# PM12_P1V0.net
KiCad netlist of a schematic drawn in Altium Designer
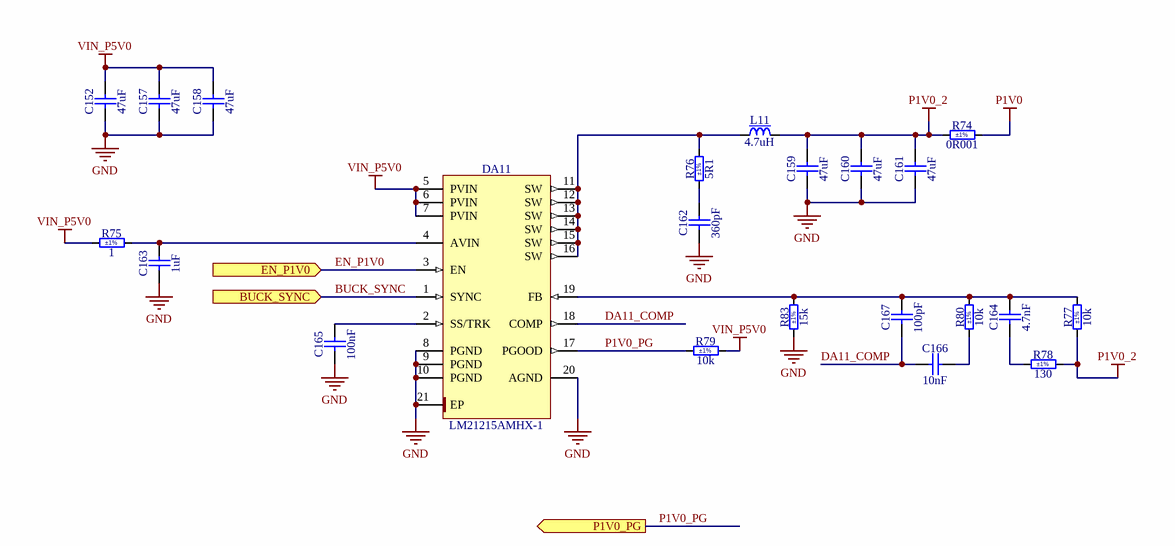
[diagram p0: PM12_P1V0.SchDoc]

(export (version "E")
  (design (tool "Eeschema 10.0.6"))
  (components
    (comp (ref "C152")
      (value "47uF")
      (footprint "CAPC3225X270N")
      (description "Non-polarised capacitor")
      (fields
        (field (name "PART NUMBER") "CC1210_47UF_16V_20%_X5R")
        (field (name "VOLTAGE") "16V")
        (field (name "AUTHOR") "CERN DEM MR")
      )
      (libsource (lib "Capacitors") (part "Capacitor - non polarized"))
    )
    (comp (ref "C157")
      (value "47uF")
      (footprint "CAPC3225X270N")
      (description "Non-polarised capacitor")
      (fields
        (field (name "PART NUMBER") "CC1210_47UF_16V_20%_X5R")
        (field (name "VOLTAGE") "16V")
        (field (name "AUTHOR") "CERN DEM MR")
      )
      (libsource (lib "Capacitors") (part "Capacitor - non polarized"))
    )
    (comp (ref "C158")
      (value "47uF")
      (footprint "CAPC3225X270N")
      (description "Non-polarised capacitor")
      (fields
        (field (name "PART NUMBER") "CC1210_47UF_16V_20%_X5R")
        (field (name "VOLTAGE") "16V")
        (field (name "AUTHOR") "CERN DEM MR")
      )
      (libsource (lib "Capacitors") (part "Capacitor - non polarized"))
    )
    (comp (ref "C159")
      (value "47uF")
      (footprint "CAPC3225X270N")
      (description "Non-polarised capacitor")
      (fields
        (field (name "PART NUMBER") "CC1210_47UF_16V_20%_X5R")
        (field (name "VOLTAGE") "16V")
        (field (name "AUTHOR") "CERN DEM MR")
      )
      (libsource (lib "Capacitors") (part "Capacitor - non polarized"))
    )
    (comp (ref "C160")
      (value "47uF")
      (footprint "CAPC3225X270N")
      (description "Non-polarised capacitor")
      (fields
        (field (name "PART NUMBER") "CC1210_47UF_16V_20%_X5R")
        (field (name "VOLTAGE") "16V")
        (field (name "AUTHOR") "CERN DEM MR")
      )
      (libsource (lib "Capacitors") (part "Capacitor - non polarized"))
    )
    (comp (ref "C161")
      (value "47uF")
      (footprint "CAPC3225X270N")
      (description "Non-polarised capacitor")
      (fields
        (field (name "PART NUMBER") "CC1210_47UF_16V_20%_X5R")
        (field (name "VOLTAGE") "16V")
        (field (name "AUTHOR") "CERN DEM MR")
      )
      (libsource (lib "Capacitors") (part "Capacitor - non polarized"))
    )
    (comp (ref "C162")
      (value "360pF")
      (footprint "CAPC2013X145N")
      (description "Non-polarised capacitor")
      (fields
        (field (name "PART NUMBER") "CC0805_360PF_50V_5%_C0G")
        (field (name "VOLTAGE") "50V")
        (field (name "AUTHOR") "CERN DEM HF")
      )
      (libsource (lib "Capacitors") (part "Capacitor - non polarized"))
    )
    (comp (ref "C163")
      (value "1uF")
      (footprint "CAPC2012X140N")
      (description "Non-polarised capacitor")
      (fields
        (field (name "PART NUMBER") "CC0805_1UF_25V_10%_X7R")
        (field (name "VOLTAGE") "25V")
        (field (name "AUTHOR") "CERN DEM JLC")
      )
      (libsource (lib "Capacitors") (part "Capacitor - non polarized"))
    )
    (comp (ref "C164")
      (value "4.7nF")
      (footprint "CAPC2012X135N")
      (description "Non-polarised capacitor")
      (fields
        (field (name "PART NUMBER") "CC0805_4.7NF_50V_10%_X7R")
        (field (name "VOLTAGE") "50V")
        (field (name "AUTHOR") "CERN DEM JLC")
      )
      (libsource (lib "Capacitors") (part "Capacitor - non polarized"))
    )
    (comp (ref "C165")
      (value "100nF")
      (footprint "CAPC2012X135N")
      (description "Non-polarised capacitor")
      (fields
        (field (name "PART NUMBER") "CC0805_100NF_50V_10%_X7R")
        (field (name "VOLTAGE") "50V")
        (field (name "AUTHOR") "CERN DEM JLC")
      )
      (libsource (lib "Capacitors") (part "Capacitor - non polarized"))
    )
    (comp (ref "C166")
      (value "10nF")
      (footprint "CAPC2012X135N")
      (description "Non-polarised capacitor")
      (fields
        (field (name "PART NUMBER") "CC0805_10NF_50V_10%_X7R")
        (field (name "VOLTAGE") "50V")
        (field (name "AUTHOR") "CERN DEM JLC")
      )
      (libsource (lib "Capacitors") (part "Capacitor - non polarized"))
    )
    (comp (ref "C167")
      (value "100pF")
      (footprint "CAPC2012X135N")
      (description "Non-polarised capacitor")
      (fields
        (field (name "PART NUMBER") "CC0805_100PF_50V_5%_NP0")
        (field (name "VOLTAGE") "50V")
        (field (name "AUTHOR") "CERN DEM JLC")
      )
      (libsource (lib "Capacitors") (part "Capacitor - non polarized"))
    )
    (comp (ref "DA11")
      (value "LM21215AMHX-1")
      (footprint "TEXAS_PWP0020AA")
      (description "2.95-V To 5.5-V, 12-A, Voltage-Mode Synchronous Buck Regulator with Frequency Synchronization")
      (fields (field (name "MANUFACTURER") "TEXAS INSTRUMENTS") (field (name "AUTHOR") "CERN DEM HF"))
      (libsource (lib "ICs And Semiconductors") (part "LM21215"))
    )
    (comp (ref "L11")
      (value "4.7uH")
      (footprint "INDM172170X700N")
      (description "Inductor With Core")
      (fields
        (field (name "PART NUMBER") "IND6767_4.7UH_20%_VISHAY_IHLP-6767GZ-11")
        (field (name "POWER") "30A")
        (field (name "AUTHOR") "CERN DEM HF")
      )
      (libsource (lib "Inductors & Transformers") (part "Inductor With Magnetic core"))
    )
    (comp (ref "R74")
      (value "0R001")
      (footprint "RESC_BOURNS_CRE2512_0R001-0R004")
      (description "Resistor - 1%")
      (fields
        (field (name "TOLERANCE") "±1%")
        (field (name "PART NUMBER") "R2512_0R001_1%_3W_50PPM_BOURNS_CRE2512")
        (field (name "POWER") "3W")
        (field (name "AUTHOR") "CERN DEM BC")
      )
      (libsource (lib "Resistors") (part "Resistor - 1%"))
    )
    (comp (ref "R75")
      (value "1")
      (footprint "RESC2012X60N")
      (description "Resistor - 1%")
      (fields
        (field (name "TOLERANCE") "±1%")
        (field (name "PART NUMBER") "R0805_1R_1%_0.125W_100PPM")
        (field (name "POWER") "0.125W")
        (field (name "AUTHOR") "CERN DEM HF")
      )
      (libsource (lib "Resistors") (part "Resistor - 1%"))
    )
    (comp (ref "R76")
      (value "5R1")
      (footprint "RESC2012X60N")
      (description "Resistor - 1%")
      (fields
        (field (name "TOLERANCE") "±1%")
        (field (name "PART NUMBER") "R0805_5R1_1%_0.125W_100PPM")
        (field (name "POWER") "0.125W")
        (field (name "AUTHOR") "CERN DEM HF")
      )
      (libsource (lib "Resistors") (part "Resistor - 1%"))
    )
    (comp (ref "R77")
      (value "10k")
      (footprint "RESC2012X60N")
      (description "Resistor - 1%")
      (fields
        (field (name "TOLERANCE") "±1%")
        (field (name "PART NUMBER") "R0805_10K_1%_0.125W_100PPM")
        (field (name "POWER") "0.125W")
        (field (name "AUTHOR") "CERN DEM JLC")
      )
      (libsource (lib "Resistors") (part "Resistor - 1%"))
    )
    (comp (ref "R78")
      (value "130")
      (footprint "RESC2012X60N")
      (description "Resistor - 1%")
      (fields
        (field (name "TOLERANCE") "±1%")
        (field (name "PART NUMBER") "R0805_130R_1%_0.125W_100PPM")
        (field (name "POWER") "0.125W")
        (field (name "AUTHOR") "CERN DEM JLC")
      )
      (libsource (lib "Resistors") (part "Resistor - 1%"))
    )
    (comp (ref "R79")
      (value "10k")
      (footprint "RESC2012X60N")
      (description "Resistor - 1%")
      (fields
        (field (name "TOLERANCE") "±1%")
        (field (name "PART NUMBER") "R0805_10K_1%_0.125W_100PPM")
        (field (name "POWER") "0.125W")
        (field (name "AUTHOR") "CERN DEM JLC")
      )
      (libsource (lib "Resistors") (part "Resistor - 1%"))
    )
    (comp (ref "R80")
      (value "10k")
      (footprint "RESC2012X60N")
      (description "Resistor - 1%")
      (fields
        (field (name "TOLERANCE") "±1%")
        (field (name "PART NUMBER") "R0805_10K_1%_0.125W_100PPM")
        (field (name "POWER") "0.125W")
        (field (name "AUTHOR") "CERN DEM JLC")
      )
      (libsource (lib "Resistors") (part "Resistor - 1%"))
    )
    (comp (ref "R83")
      (value "15k")
      (footprint "RESC2012X60N")
      (description "Resistor - 1%")
      (fields
        (field (name "TOLERANCE") "±1%")
        (field (name "PART NUMBER") "R0805_15K_1%_0.125W_100PPM")
        (field (name "POWER") "0.125W")
        (field (name "AUTHOR") "CERN DEM JLC")
      )
      (libsource (lib "Resistors") (part "Resistor - 1%"))
    )
  )
  (nets
    (net (code "1") (name "/BUCK_SYNC") (class "Default")
      (node (ref "DA11") (pin "1") (pinfunction "SYNC_1") (pintype "input"))
    )
    (net (code "2") (name "/DA11_COMP") (class "Default")
      (node (ref "C166") (pin "1") (pinfunction "1_1") (pintype "passive"))
      (node (ref "C167") (pin "1") (pinfunction "1_1") (pintype "passive"))
      (node (ref "DA11") (pin "18") (pinfunction "COMP_18") (pintype "output"))
    )
    (net (code "3") (name "/EN_P1V0") (class "Default")
      (node (ref "DA11") (pin "3") (pinfunction "EN_3") (pintype "input"))
    )
    (net (code "4") (name "/P1V0_PG") (class "Default")
      (node (ref "DA11") (pin "17") (pinfunction "PGOOD_17") (pintype "output"))
      (node (ref "R79") (pin "1") (pinfunction "1_1") (pintype "passive"))
    )
    (net (code "5") (name "GND") (class "Default")
      (node (ref "C152") (pin "1") (pinfunction "1_1") (pintype "passive"))
      (node (ref "C157") (pin "1") (pinfunction "1_1") (pintype "passive"))
      (node (ref "C158") (pin "1") (pinfunction "1_1") (pintype "passive"))
      (node (ref "C159") (pin "1") (pinfunction "1_1") (pintype "passive"))
      (node (ref "C160") (pin "1") (pinfunction "1_1") (pintype "passive"))
      (node (ref "C161") (pin "1") (pinfunction "1_1") (pintype "passive"))
      (node (ref "C162") (pin "1") (pinfunction "1_1") (pintype "passive"))
      (node (ref "C163") (pin "1") (pinfunction "1_1") (pintype "passive"))
      (node (ref "C165") (pin "1") (pinfunction "1_1") (pintype "passive"))
      (node (ref "DA11") (pin "10") (pinfunction "PGND_10") (pintype "power_in"))
      (node (ref "DA11") (pin "20") (pinfunction "AGND_20") (pintype "power_in"))
      (node (ref "DA11") (pin "21") (pinfunction "EP_21") (pintype "power_in"))
      (node (ref "DA11") (pin "8") (pinfunction "PGND_8") (pintype "power_in"))
      (node (ref "DA11") (pin "9") (pinfunction "PGND_9") (pintype "power_in"))
      (node (ref "R83") (pin "1") (pinfunction "1_1") (pintype "passive"))
    )
    (net (code "6") (name "Net-(C162-Pad2)") (class "Default")
      (node (ref "C162") (pin "2") (pinfunction "2_2") (pintype "passive"))
      (node (ref "R76") (pin "1") (pinfunction "1_1") (pintype "passive"))
    )
    (net (code "7") (name "Net-(C164-Pad1)") (class "Default")
      (node (ref "C164") (pin "1") (pinfunction "1_1") (pintype "passive"))
      (node (ref "R78") (pin "1") (pinfunction "1_1") (pintype "passive"))
    )
    (net (code "8") (name "Net-(C166-Pad2)") (class "Default")
      (node (ref "C166") (pin "2") (pinfunction "2_2") (pintype "passive"))
      (node (ref "R80") (pin "1") (pinfunction "1_1") (pintype "passive"))
    )
    (net (code "9") (name "Net-(DA11-AVIN)") (class "Default")
      (node (ref "C163") (pin "2") (pinfunction "2_2") (pintype "passive"))
      (node (ref "DA11") (pin "4") (pinfunction "AVIN_4") (pintype "power_in"))
      (node (ref "R75") (pin "2") (pinfunction "2_2") (pintype "passive"))
    )
    (net (code "10") (name "Net-(DA11-FB)") (class "Default")
      (node (ref "C164") (pin "2") (pinfunction "2_2") (pintype "passive"))
      (node (ref "C167") (pin "2") (pinfunction "2_2") (pintype "passive"))
      (node (ref "DA11") (pin "19") (pinfunction "FB_19") (pintype "input"))
      (node (ref "R77") (pin "2") (pinfunction "2_2") (pintype "passive"))
      (node (ref "R80") (pin "2") (pinfunction "2_2") (pintype "passive"))
      (node (ref "R83") (pin "2") (pinfunction "2_2") (pintype "passive"))
    )
    (net (code "11") (name "Net-(DA11-SS{slash}TRK)") (class "Default")
      (node (ref "C165") (pin "2") (pinfunction "2_2") (pintype "passive"))
      (node (ref "DA11") (pin "2") (pinfunction "SS/TRK_2") (pintype "input"))
    )
    (net (code "12") (name "Net-(DA11-SW-Pad11)") (class "Default")
      (node (ref "DA11") (pin "11") (pinfunction "SW_11") (pintype "output"))
      (node (ref "DA11") (pin "12") (pinfunction "SW_12") (pintype "output"))
      (node (ref "DA11") (pin "13") (pinfunction "SW_13") (pintype "output"))
      (node (ref "DA11") (pin "14") (pinfunction "SW_14") (pintype "output"))
      (node (ref "DA11") (pin "15") (pinfunction "SW_15") (pintype "output"))
      (node (ref "DA11") (pin "16") (pinfunction "SW_16") (pintype "output"))
      (node (ref "L11") (pin "1") (pinfunction "1_1") (pintype "passive"))
      (node (ref "R76") (pin "2") (pinfunction "2_2") (pintype "passive"))
    )
    (net (code "13") (name "P1V0") (class "Default")
      (node (ref "R74") (pin "2") (pinfunction "2_2") (pintype "passive"))
    )
    (net (code "14") (name "P1V0_2") (class "Default")
      (node (ref "C159") (pin "2") (pinfunction "2_2") (pintype "passive"))
      (node (ref "C160") (pin "2") (pinfunction "2_2") (pintype "passive"))
      (node (ref "C161") (pin "2") (pinfunction "2_2") (pintype "passive"))
      (node (ref "L11") (pin "2") (pinfunction "2_2") (pintype "passive"))
      (node (ref "R74") (pin "1") (pinfunction "1_1") (pintype "passive"))
      (node (ref "R77") (pin "1") (pinfunction "1_1") (pintype "passive"))
      (node (ref "R78") (pin "2") (pinfunction "2_2") (pintype "passive"))
    )
    (net (code "15") (name "VIN_P5V0") (class "Default")
      (node (ref "C152") (pin "2") (pinfunction "2_2") (pintype "passive"))
      (node (ref "C157") (pin "2") (pinfunction "2_2") (pintype "passive"))
      (node (ref "C158") (pin "2") (pinfunction "2_2") (pintype "passive"))
      (node (ref "DA11") (pin "5") (pinfunction "PVIN_5") (pintype "power_in"))
      (node (ref "DA11") (pin "6") (pinfunction "PVIN_6") (pintype "power_in"))
      (node (ref "DA11") (pin "7") (pinfunction "PVIN_7") (pintype "power_in"))
      (node (ref "R75") (pin "1") (pinfunction "1_1") (pintype "passive"))
      (node (ref "R79") (pin "2") (pinfunction "2_2") (pintype "passive"))
    )
  )
)
